# FlightComputer_PowerDistributionBoard_Re.net
KiCad netlist of a schematic drawn in EAGLE
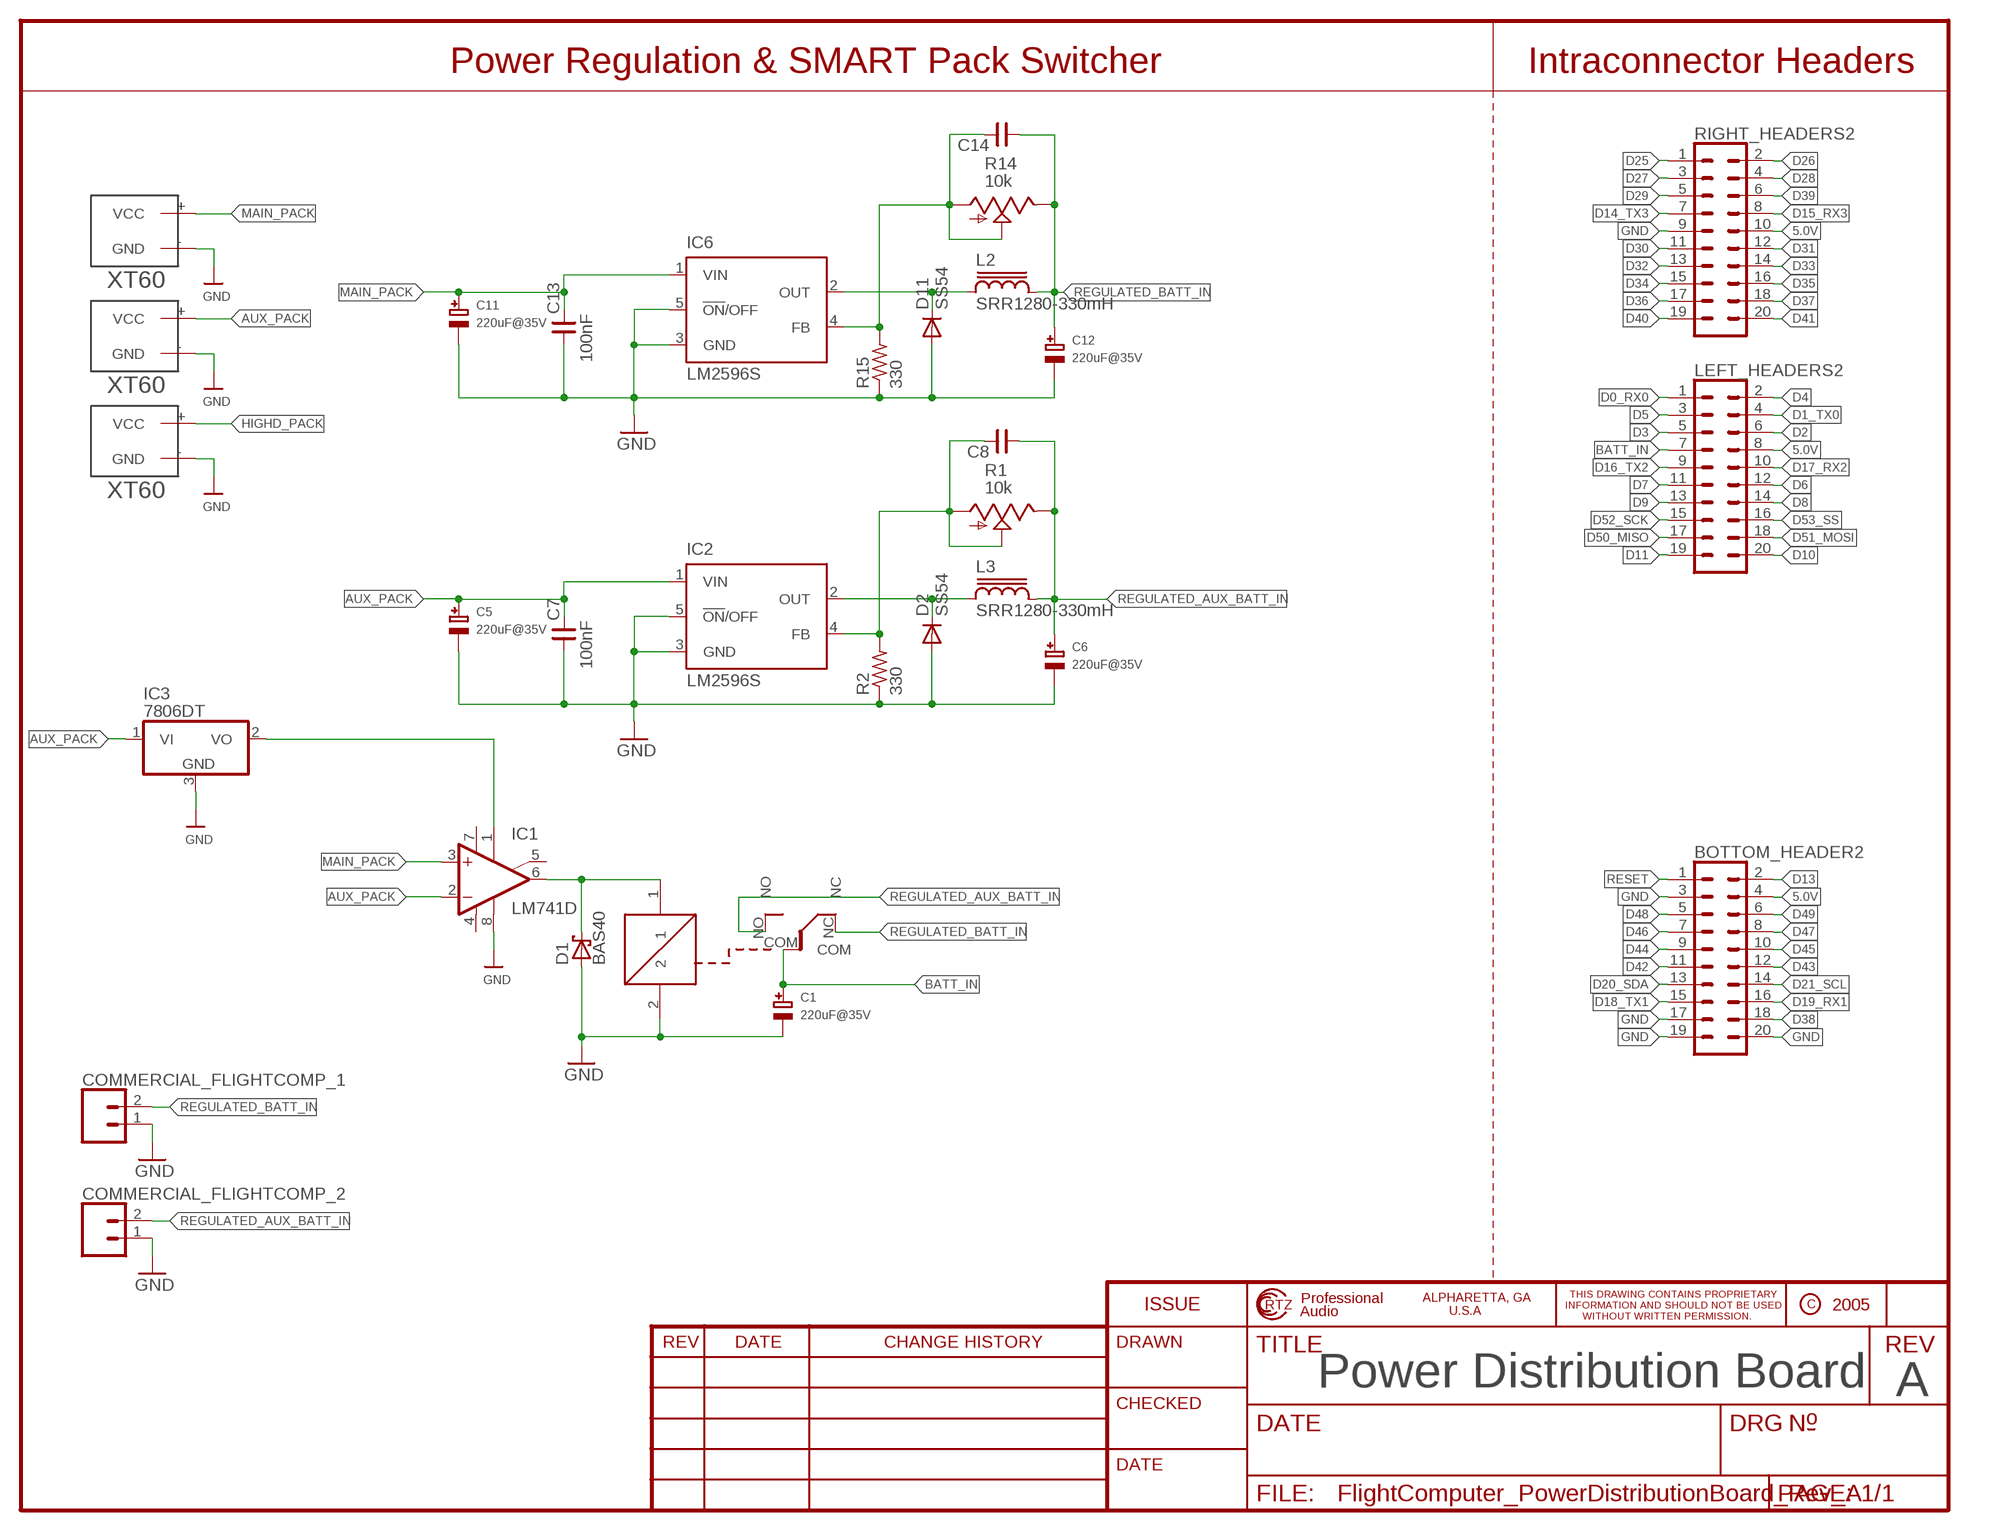
[diagram p0: schematic, sheet 1]

(export (version "E")
  (design (tool "Eeschema 10.0.6"))
  (components
    (comp (ref "BOTTOM_HEADER2")
      (value "CONN_10X2")
      (footprint "eagle-import:2X10")
      (libsource (lib "eagle-import") (part "CONN_10X2"))
    )
    (comp (ref "C1")
      (value "220uF@35V")
      (footprint "eagle-import:PANASONIC_D")
      (libsource (lib "eagle-import") (part "CAP_ELECTROLYTICPANASONIC_D"))
    )
    (comp (ref "C5")
      (value "220uF@35V")
      (footprint "eagle-import:PANASONIC_D")
      (libsource (lib "eagle-import") (part "CAP_ELECTROLYTICPANASONIC_D"))
    )
    (comp (ref "C6")
      (value "220uF@35V")
      (footprint "eagle-import:PANASONIC_D")
      (libsource (lib "eagle-import") (part "CAP_ELECTROLYTICPANASONIC_D"))
    )
    (comp (ref "C7")
      (value "100nF")
      (footprint "eagle-import:0603")
      (libsource (lib "eagle-import") (part "CNP-0603"))
    )
    (comp (ref "C8")
      (value "CNP-0603")
      (footprint "eagle-import:0603")
      (libsource (lib "eagle-import") (part "CNP-0603"))
    )
    (comp (ref "C11")
      (value "220uF@35V")
      (footprint "eagle-import:PANASONIC_D")
      (libsource (lib "eagle-import") (part "CAP_ELECTROLYTICPANASONIC_D"))
    )
    (comp (ref "C12")
      (value "220uF@35V")
      (footprint "eagle-import:PANASONIC_D")
      (libsource (lib "eagle-import") (part "CAP_ELECTROLYTICPANASONIC_D"))
    )
    (comp (ref "C13")
      (value "100nF")
      (footprint "eagle-import:0603")
      (libsource (lib "eagle-import") (part "CNP-0603"))
    )
    (comp (ref "C14")
      (value "CNP-0603")
      (footprint "eagle-import:0603")
      (libsource (lib "eagle-import") (part "CNP-0603"))
    )
    (comp (ref "COMMERCIAL_FLIGHTCOMP_1")
      (value "CONN_02")
      (footprint "eagle-import:1X02")
      (libsource (lib "eagle-import") (part "CONN_02"))
    )
    (comp (ref "COMMERCIAL_FLIGHTCOMP_2")
      (value "CONN_02")
      (footprint "eagle-import:1X02")
      (libsource (lib "eagle-import") (part "CONN_02"))
    )
    (comp (ref "D1")
      (value "BAS40")
      (footprint "eagle-import:SOT23")
      (libsource (lib "eagle-import") (part "BAS40"))
    )
    (comp (ref "D2")
      (value "SS54")
      (footprint "eagle-import:DO214AB")
      (fields (field (name "MF") "Fairchild") (field (name "MPN") "S3G"))
      (libsource (lib "eagle-import") (part "S3G"))
    )
    (comp (ref "D11")
      (value "SS54")
      (footprint "eagle-import:DO214AB")
      (fields (field (name "MF") "Fairchild") (field (name "MPN") "S3G"))
      (libsource (lib "eagle-import") (part "S3G"))
    )
    (comp (ref "IC1")
      (value "LM741D")
      (footprint "eagle-import:SO08")
      (libsource (lib "eagle-import") (part "741DLM"))
    )
    (comp (ref "IC2")
      (value "LM2596S")
      (footprint "eagle-import:TO263-5")
      (fields (field (name "MF") "NATIONAL SEMICONDUCTOR") (field (name "MPN") "LM2596S-ADJ/NOPB"))
      (libsource (lib "eagle-import") (part "LM2596S"))
    )
    (comp (ref "IC3")
      (value "7806DT")
      (footprint "eagle-import:TO252")
      (libsource (lib "eagle-import") (part "78DT06"))
    )
    (comp (ref "IC6")
      (value "LM2596S")
      (footprint "eagle-import:TO263-5")
      (fields (field (name "MF") "NATIONAL SEMICONDUCTOR") (field (name "MPN") "LM2596S-ADJ/NOPB"))
      (libsource (lib "eagle-import") (part "LM2596S"))
    )
    (comp (ref "L2")
      (value "SRR1280-330mH")
      (footprint "eagle-import:SRR1280")
      (libsource (lib "eagle-import") (part "SRR1280"))
    )
    (comp (ref "L3")
      (value "SRR1280-330mH")
      (footprint "eagle-import:SRR1280")
      (libsource (lib "eagle-import") (part "SRR1280"))
    )
    (comp (ref "LEFT_HEADERS2")
      (value "CONN_10X2")
      (footprint "eagle-import:2X10")
      (libsource (lib "eagle-import") (part "CONN_10X2"))
    )
    (comp (ref "R1")
      (value "10k")
      (footprint "eagle-import:S64W")
      (libsource (lib "eagle-import") (part "TRIM_US-S64W"))
    )
    (comp (ref "R2")
      (value "330")
      (footprint "eagle-import:R0603")
      (libsource (lib "eagle-import") (part "R-US_R0603"))
    )
    (comp (ref "R14")
      (value "10k")
      (footprint "eagle-import:S64W")
      (libsource (lib "eagle-import") (part "TRIM_US-S64W"))
    )
    (comp (ref "R15")
      (value "330")
      (footprint "eagle-import:R0603")
      (libsource (lib "eagle-import") (part "R-US_R0603"))
    )
    (comp (ref "RIGHT_HEADERS2")
      (value "CONN_10X2")
      (footprint "eagle-import:2X10")
      (libsource (lib "eagle-import") (part "CONN_10X2"))
    )
    (comp (ref "U$2")
      (value "XT60")
      (footprint "eagle-import:XT60")
      (libsource (lib "eagle-import") (part "XT60"))
    )
    (comp (ref "U$3")
      (value "XT60")
      (footprint "eagle-import:XT60")
      (libsource (lib "eagle-import") (part "XT60"))
    )
    (comp (ref "U$4")
      (value "XT60")
      (footprint "eagle-import:XT60")
      (libsource (lib "eagle-import") (part "XT60"))
    )
    (comp (ref "U$14")
      (value "RW-SH")
      (footprint "eagle-import:RW-SH")
      (libsource (lib "eagle-import") (part "RW-SH"))
    )
  )
  (nets
    (net (code "1") (name "/V+") (class "Default")
      (node (ref "IC1") (pin "7") (pinfunction "V+_7") (pintype "power_in"))
    )
    (net (code "2") (name "/V-") (class "Default")
      (node (ref "IC1") (pin "4") (pinfunction "V-_4") (pintype "power_in"))
    )
    (net (code "3") (name "5.0V") (class "Default")
      (node (ref "BOTTOM_HEADER2") (pin "4") (pinfunction "4_4") (pintype "passive"))
      (node (ref "LEFT_HEADERS2") (pin "8") (pinfunction "8_8") (pintype "passive"))
      (node (ref "RIGHT_HEADERS2") (pin "10") (pinfunction "10_10") (pintype "passive"))
    )
    (net (code "4") (name "AUX_PACK") (class "Default")
      (node (ref "C5") (pin "+") (pinfunction "+_+") (pintype "passive"))
      (node (ref "C7") (pin "2") (pinfunction "2_2") (pintype "passive"))
      (node (ref "IC1") (pin "2") (pinfunction "-IN_2") (pintype "input"))
      (node (ref "IC2") (pin "1") (pinfunction "VIN_1") (pintype "input"))
      (node (ref "IC3") (pin "1") (pinfunction "VI_1") (pintype "input"))
      (node (ref "U$3") (pin "+") (pinfunction "VCC_+") (pintype "bidirectional"))
    )
    (net (code "5") (name "BATT_IN") (class "Default")
      (node (ref "C1") (pin "+") (pinfunction "+_+") (pintype "passive"))
      (node (ref "LEFT_HEADERS2") (pin "7") (pinfunction "7_7") (pintype "passive"))
      (node (ref "U$14") (pin "COM") (pinfunction "COM_COM") (pintype "bidirectional"))
    )
    (net (code "6") (name "D0_RX0") (class "Default")
      (node (ref "LEFT_HEADERS2") (pin "1") (pinfunction "1_1") (pintype "passive"))
    )
    (net (code "7") (name "D1_TX0") (class "Default")
      (node (ref "LEFT_HEADERS2") (pin "4") (pinfunction "4_4") (pintype "passive"))
    )
    (net (code "8") (name "D2") (class "Default")
      (node (ref "LEFT_HEADERS2") (pin "6") (pinfunction "6_6") (pintype "passive"))
    )
    (net (code "9") (name "D3") (class "Default")
      (node (ref "LEFT_HEADERS2") (pin "5") (pinfunction "5_5") (pintype "passive"))
    )
    (net (code "10") (name "D4") (class "Default")
      (node (ref "LEFT_HEADERS2") (pin "2") (pinfunction "2_2") (pintype "passive"))
    )
    (net (code "11") (name "D5") (class "Default")
      (node (ref "LEFT_HEADERS2") (pin "3") (pinfunction "3_3") (pintype "passive"))
    )
    (net (code "12") (name "D6") (class "Default")
      (node (ref "LEFT_HEADERS2") (pin "12") (pinfunction "12_12") (pintype "passive"))
    )
    (net (code "13") (name "D7") (class "Default")
      (node (ref "LEFT_HEADERS2") (pin "11") (pinfunction "11_11") (pintype "passive"))
    )
    (net (code "14") (name "D8") (class "Default")
      (node (ref "LEFT_HEADERS2") (pin "14") (pinfunction "14_14") (pintype "passive"))
    )
    (net (code "15") (name "D9") (class "Default")
      (node (ref "LEFT_HEADERS2") (pin "13") (pinfunction "13_13") (pintype "passive"))
    )
    (net (code "16") (name "D10") (class "Default")
      (node (ref "LEFT_HEADERS2") (pin "20") (pinfunction "20_20") (pintype "passive"))
    )
    (net (code "17") (name "D11") (class "Default")
      (node (ref "LEFT_HEADERS2") (pin "19") (pinfunction "19_19") (pintype "passive"))
    )
    (net (code "18") (name "D13") (class "Default")
      (node (ref "BOTTOM_HEADER2") (pin "2") (pinfunction "2_2") (pintype "passive"))
    )
    (net (code "19") (name "D14_TX3") (class "Default")
      (node (ref "RIGHT_HEADERS2") (pin "7") (pinfunction "7_7") (pintype "passive"))
    )
    (net (code "20") (name "D15_RX3") (class "Default")
      (node (ref "RIGHT_HEADERS2") (pin "8") (pinfunction "8_8") (pintype "passive"))
    )
    (net (code "21") (name "D16_TX2") (class "Default")
      (node (ref "LEFT_HEADERS2") (pin "9") (pinfunction "9_9") (pintype "passive"))
    )
    (net (code "22") (name "D17_RX2") (class "Default")
      (node (ref "LEFT_HEADERS2") (pin "10") (pinfunction "10_10") (pintype "passive"))
    )
    (net (code "23") (name "D18_TX1") (class "Default")
      (node (ref "BOTTOM_HEADER2") (pin "15") (pinfunction "15_15") (pintype "passive"))
    )
    (net (code "24") (name "D19_RX1") (class "Default")
      (node (ref "BOTTOM_HEADER2") (pin "16") (pinfunction "16_16") (pintype "passive"))
    )
    (net (code "25") (name "D20_SDA") (class "Default")
      (node (ref "BOTTOM_HEADER2") (pin "13") (pinfunction "13_13") (pintype "passive"))
    )
    (net (code "26") (name "D21_SCL") (class "Default")
      (node (ref "BOTTOM_HEADER2") (pin "14") (pinfunction "14_14") (pintype "passive"))
    )
    (net (code "27") (name "D25") (class "Default")
      (node (ref "RIGHT_HEADERS2") (pin "1") (pinfunction "1_1") (pintype "passive"))
    )
    (net (code "28") (name "D26") (class "Default")
      (node (ref "RIGHT_HEADERS2") (pin "2") (pinfunction "2_2") (pintype "passive"))
    )
    (net (code "29") (name "D27") (class "Default")
      (node (ref "RIGHT_HEADERS2") (pin "3") (pinfunction "3_3") (pintype "passive"))
    )
    (net (code "30") (name "D28") (class "Default")
      (node (ref "RIGHT_HEADERS2") (pin "4") (pinfunction "4_4") (pintype "passive"))
    )
    (net (code "31") (name "D29") (class "Default")
      (node (ref "RIGHT_HEADERS2") (pin "5") (pinfunction "5_5") (pintype "passive"))
    )
    (net (code "32") (name "D30") (class "Default")
      (node (ref "RIGHT_HEADERS2") (pin "11") (pinfunction "11_11") (pintype "passive"))
    )
    (net (code "33") (name "D31") (class "Default")
      (node (ref "RIGHT_HEADERS2") (pin "12") (pinfunction "12_12") (pintype "passive"))
    )
    (net (code "34") (name "D32") (class "Default")
      (node (ref "RIGHT_HEADERS2") (pin "13") (pinfunction "13_13") (pintype "passive"))
    )
    (net (code "35") (name "D33") (class "Default")
      (node (ref "RIGHT_HEADERS2") (pin "14") (pinfunction "14_14") (pintype "passive"))
    )
    (net (code "36") (name "D34") (class "Default")
      (node (ref "RIGHT_HEADERS2") (pin "15") (pinfunction "15_15") (pintype "passive"))
    )
    (net (code "37") (name "D35") (class "Default")
      (node (ref "RIGHT_HEADERS2") (pin "16") (pinfunction "16_16") (pintype "passive"))
    )
    (net (code "38") (name "D36") (class "Default")
      (node (ref "RIGHT_HEADERS2") (pin "17") (pinfunction "17_17") (pintype "passive"))
    )
    (net (code "39") (name "D37") (class "Default")
      (node (ref "RIGHT_HEADERS2") (pin "18") (pinfunction "18_18") (pintype "passive"))
    )
    (net (code "40") (name "D38") (class "Default")
      (node (ref "BOTTOM_HEADER2") (pin "18") (pinfunction "18_18") (pintype "passive"))
    )
    (net (code "41") (name "D39") (class "Default")
      (node (ref "RIGHT_HEADERS2") (pin "6") (pinfunction "6_6") (pintype "passive"))
    )
    (net (code "42") (name "D40") (class "Default")
      (node (ref "RIGHT_HEADERS2") (pin "19") (pinfunction "19_19") (pintype "passive"))
    )
    (net (code "43") (name "D41") (class "Default")
      (node (ref "RIGHT_HEADERS2") (pin "20") (pinfunction "20_20") (pintype "passive"))
    )
    (net (code "44") (name "D42") (class "Default")
      (node (ref "BOTTOM_HEADER2") (pin "11") (pinfunction "11_11") (pintype "passive"))
    )
    (net (code "45") (name "D43") (class "Default")
      (node (ref "BOTTOM_HEADER2") (pin "12") (pinfunction "12_12") (pintype "passive"))
    )
    (net (code "46") (name "D44") (class "Default")
      (node (ref "BOTTOM_HEADER2") (pin "9") (pinfunction "9_9") (pintype "passive"))
    )
    (net (code "47") (name "D45") (class "Default")
      (node (ref "BOTTOM_HEADER2") (pin "10") (pinfunction "10_10") (pintype "passive"))
    )
    (net (code "48") (name "D46") (class "Default")
      (node (ref "BOTTOM_HEADER2") (pin "7") (pinfunction "7_7") (pintype "passive"))
    )
    (net (code "49") (name "D47") (class "Default")
      (node (ref "BOTTOM_HEADER2") (pin "8") (pinfunction "8_8") (pintype "passive"))
    )
    (net (code "50") (name "D48") (class "Default")
      (node (ref "BOTTOM_HEADER2") (pin "5") (pinfunction "5_5") (pintype "passive"))
    )
    (net (code "51") (name "D49") (class "Default")
      (node (ref "BOTTOM_HEADER2") (pin "6") (pinfunction "6_6") (pintype "passive"))
    )
    (net (code "52") (name "D50_MISO") (class "Default")
      (node (ref "LEFT_HEADERS2") (pin "17") (pinfunction "17_17") (pintype "passive"))
    )
    (net (code "53") (name "D51_MOSI") (class "Default")
      (node (ref "LEFT_HEADERS2") (pin "18") (pinfunction "18_18") (pintype "passive"))
    )
    (net (code "54") (name "D52_SCK") (class "Default")
      (node (ref "LEFT_HEADERS2") (pin "15") (pinfunction "15_15") (pintype "passive"))
    )
    (net (code "55") (name "D53_SS") (class "Default")
      (node (ref "LEFT_HEADERS2") (pin "16") (pinfunction "16_16") (pintype "passive"))
    )
    (net (code "56") (name "GND") (class "Default")
      (node (ref "BOTTOM_HEADER2") (pin "17") (pinfunction "17_17") (pintype "passive"))
      (node (ref "BOTTOM_HEADER2") (pin "19") (pinfunction "19_19") (pintype "passive"))
      (node (ref "BOTTOM_HEADER2") (pin "20") (pinfunction "20_20") (pintype "passive"))
      (node (ref "BOTTOM_HEADER2") (pin "3") (pinfunction "3_3") (pintype "passive"))
      (node (ref "C1") (pin "-") (pinfunction "-_-") (pintype "passive"))
      (node (ref "C11") (pin "-") (pinfunction "-_-") (pintype "passive"))
      (node (ref "C12") (pin "-") (pinfunction "-_-") (pintype "passive"))
      (node (ref "C13") (pin "1") (pinfunction "1_1") (pintype "passive"))
      (node (ref "C5") (pin "-") (pinfunction "-_-") (pintype "passive"))
      (node (ref "C6") (pin "-") (pinfunction "-_-") (pintype "passive"))
      (node (ref "C7") (pin "1") (pinfunction "1_1") (pintype "passive"))
      (node (ref "COMMERCIAL_FLIGHTCOMP_1") (pin "1") (pinfunction "1_1") (pintype "passive"))
      (node (ref "COMMERCIAL_FLIGHTCOMP_2") (pin "1") (pinfunction "1_1") (pintype "passive"))
      (node (ref "D1") (pin "1") (pinfunction "A_1") (pintype "passive"))
      (node (ref "D11") (pin "A") (pinfunction "A_A") (pintype "passive"))
      (node (ref "D2") (pin "A") (pinfunction "A_A") (pintype "passive"))
      (node (ref "IC1") (pin "8") (pinfunction "OPT_8") (pintype "passive"))
      (node (ref "IC2") (pin "3") (pinfunction "GND_3") (pintype "power_in"))
      (node (ref "IC2") (pin "5") (pinfunction "~{ON}/OFF_5") (pintype "input"))
      (node (ref "IC3") (pin "3") (pinfunction "GND_3") (pintype "passive"))
      (node (ref "IC6") (pin "3") (pinfunction "GND_3") (pintype "power_in"))
      (node (ref "IC6") (pin "5") (pinfunction "~{ON}/OFF_5") (pintype "input"))
      (node (ref "R15") (pin "1") (pinfunction "1_1") (pintype "passive"))
      (node (ref "R2") (pin "1") (pinfunction "1_1") (pintype "passive"))
      (node (ref "RIGHT_HEADERS2") (pin "9") (pinfunction "9_9") (pintype "passive"))
      (node (ref "U$14") (pin "2") (pinfunction "2_2") (pintype "bidirectional"))
      (node (ref "U$2") (pin "-") (pinfunction "GND_-") (pintype "bidirectional"))
      (node (ref "U$3") (pin "-") (pinfunction "GND_-") (pintype "bidirectional"))
      (node (ref "U$4") (pin "-") (pinfunction "GND_-") (pintype "bidirectional"))
    )
    (net (code "57") (name "HIGHD_PACK") (class "Default")
      (node (ref "U$4") (pin "+") (pinfunction "VCC_+") (pintype "bidirectional"))
    )
    (net (code "58") (name "MAIN_PACK") (class "Default")
      (node (ref "C11") (pin "+") (pinfunction "+_+") (pintype "passive"))
      (node (ref "C13") (pin "2") (pinfunction "2_2") (pintype "passive"))
      (node (ref "IC1") (pin "3") (pinfunction "+IN_3") (pintype "input"))
      (node (ref "IC6") (pin "1") (pinfunction "VIN_1") (pintype "input"))
      (node (ref "U$2") (pin "+") (pinfunction "VCC_+") (pintype "bidirectional"))
    )
    (net (code "59") (name "Net-(D1-C)") (class "Default")
      (node (ref "D1") (pin "3") (pinfunction "C_3") (pintype "passive"))
      (node (ref "IC1") (pin "6") (pinfunction "OUT_6") (pintype "output"))
      (node (ref "U$14") (pin "1") (pinfunction "1_1") (pintype "bidirectional"))
    )
    (net (code "60") (name "Net-(IC1-ON1)") (class "Default")
      (node (ref "IC1") (pin "1") (pinfunction "ON1_1") (pintype "passive"))
      (node (ref "IC3") (pin "2") (pinfunction "VO_2") (pintype "passive"))
    )
    (net (code "61") (name "Net-(IC2-FB)") (class "Default")
      (node (ref "C8") (pin "2") (pinfunction "2_2") (pintype "passive"))
      (node (ref "IC2") (pin "4") (pinfunction "FB_4") (pintype "input"))
      (node (ref "R1") (pin "A") (pinfunction "A_A") (pintype "passive"))
      (node (ref "R1") (pin "S") (pinfunction "S_S") (pintype "passive"))
      (node (ref "R2") (pin "2") (pinfunction "2_2") (pintype "passive"))
    )
    (net (code "62") (name "Net-(IC2-OUT)") (class "Default")
      (node (ref "D2") (pin "C") (pinfunction "C_C") (pintype "passive"))
      (node (ref "IC2") (pin "2") (pinfunction "OUT_2") (pintype "output"))
      (node (ref "L3") (pin "1") (pinfunction "1_1") (pintype "passive"))
    )
    (net (code "63") (name "Net-(IC6-FB)") (class "Default")
      (node (ref "C14") (pin "2") (pinfunction "2_2") (pintype "passive"))
      (node (ref "IC6") (pin "4") (pinfunction "FB_4") (pintype "input"))
      (node (ref "R14") (pin "A") (pinfunction "A_A") (pintype "passive"))
      (node (ref "R14") (pin "S") (pinfunction "S_S") (pintype "passive"))
      (node (ref "R15") (pin "2") (pinfunction "2_2") (pintype "passive"))
    )
    (net (code "64") (name "Net-(IC6-OUT)") (class "Default")
      (node (ref "D11") (pin "C") (pinfunction "C_C") (pintype "passive"))
      (node (ref "IC6") (pin "2") (pinfunction "OUT_2") (pintype "output"))
      (node (ref "L2") (pin "1") (pinfunction "1_1") (pintype "passive"))
    )
    (net (code "65") (name "REGULATED_AUX_BATT_IN") (class "Default")
      (node (ref "C6") (pin "+") (pinfunction "+_+") (pintype "passive"))
      (node (ref "C8") (pin "1") (pinfunction "1_1") (pintype "passive"))
      (node (ref "COMMERCIAL_FLIGHTCOMP_2") (pin "2") (pinfunction "2_2") (pintype "passive"))
      (node (ref "L3") (pin "2") (pinfunction "2_2") (pintype "passive"))
      (node (ref "R1") (pin "E") (pinfunction "E_E") (pintype "passive"))
      (node (ref "U$14") (pin "NO") (pinfunction "NO_NO") (pintype "bidirectional"))
    )
    (net (code "66") (name "REGULATED_BATT_IN") (class "Default")
      (node (ref "C12") (pin "+") (pinfunction "+_+") (pintype "passive"))
      (node (ref "C14") (pin "1") (pinfunction "1_1") (pintype "passive"))
      (node (ref "COMMERCIAL_FLIGHTCOMP_1") (pin "2") (pinfunction "2_2") (pintype "passive"))
      (node (ref "L2") (pin "2") (pinfunction "2_2") (pintype "passive"))
      (node (ref "R14") (pin "E") (pinfunction "E_E") (pintype "passive"))
      (node (ref "U$14") (pin "NC") (pinfunction "NC_NC") (pintype "bidirectional"))
    )
    (net (code "67") (name "RESET") (class "Default")
      (node (ref "BOTTOM_HEADER2") (pin "1") (pinfunction "1_1") (pintype "passive"))
    )
    (net (code "68") (name "unconnected-(IC1-ON2-Pad5)") (class "Default")
      (node (ref "IC1") (pin "5") (pinfunction "ON2_5") (pintype "passive"))
    )
  )
)
